# Senaino.net
KiCad netlist of a schematic drawn in EAGLE
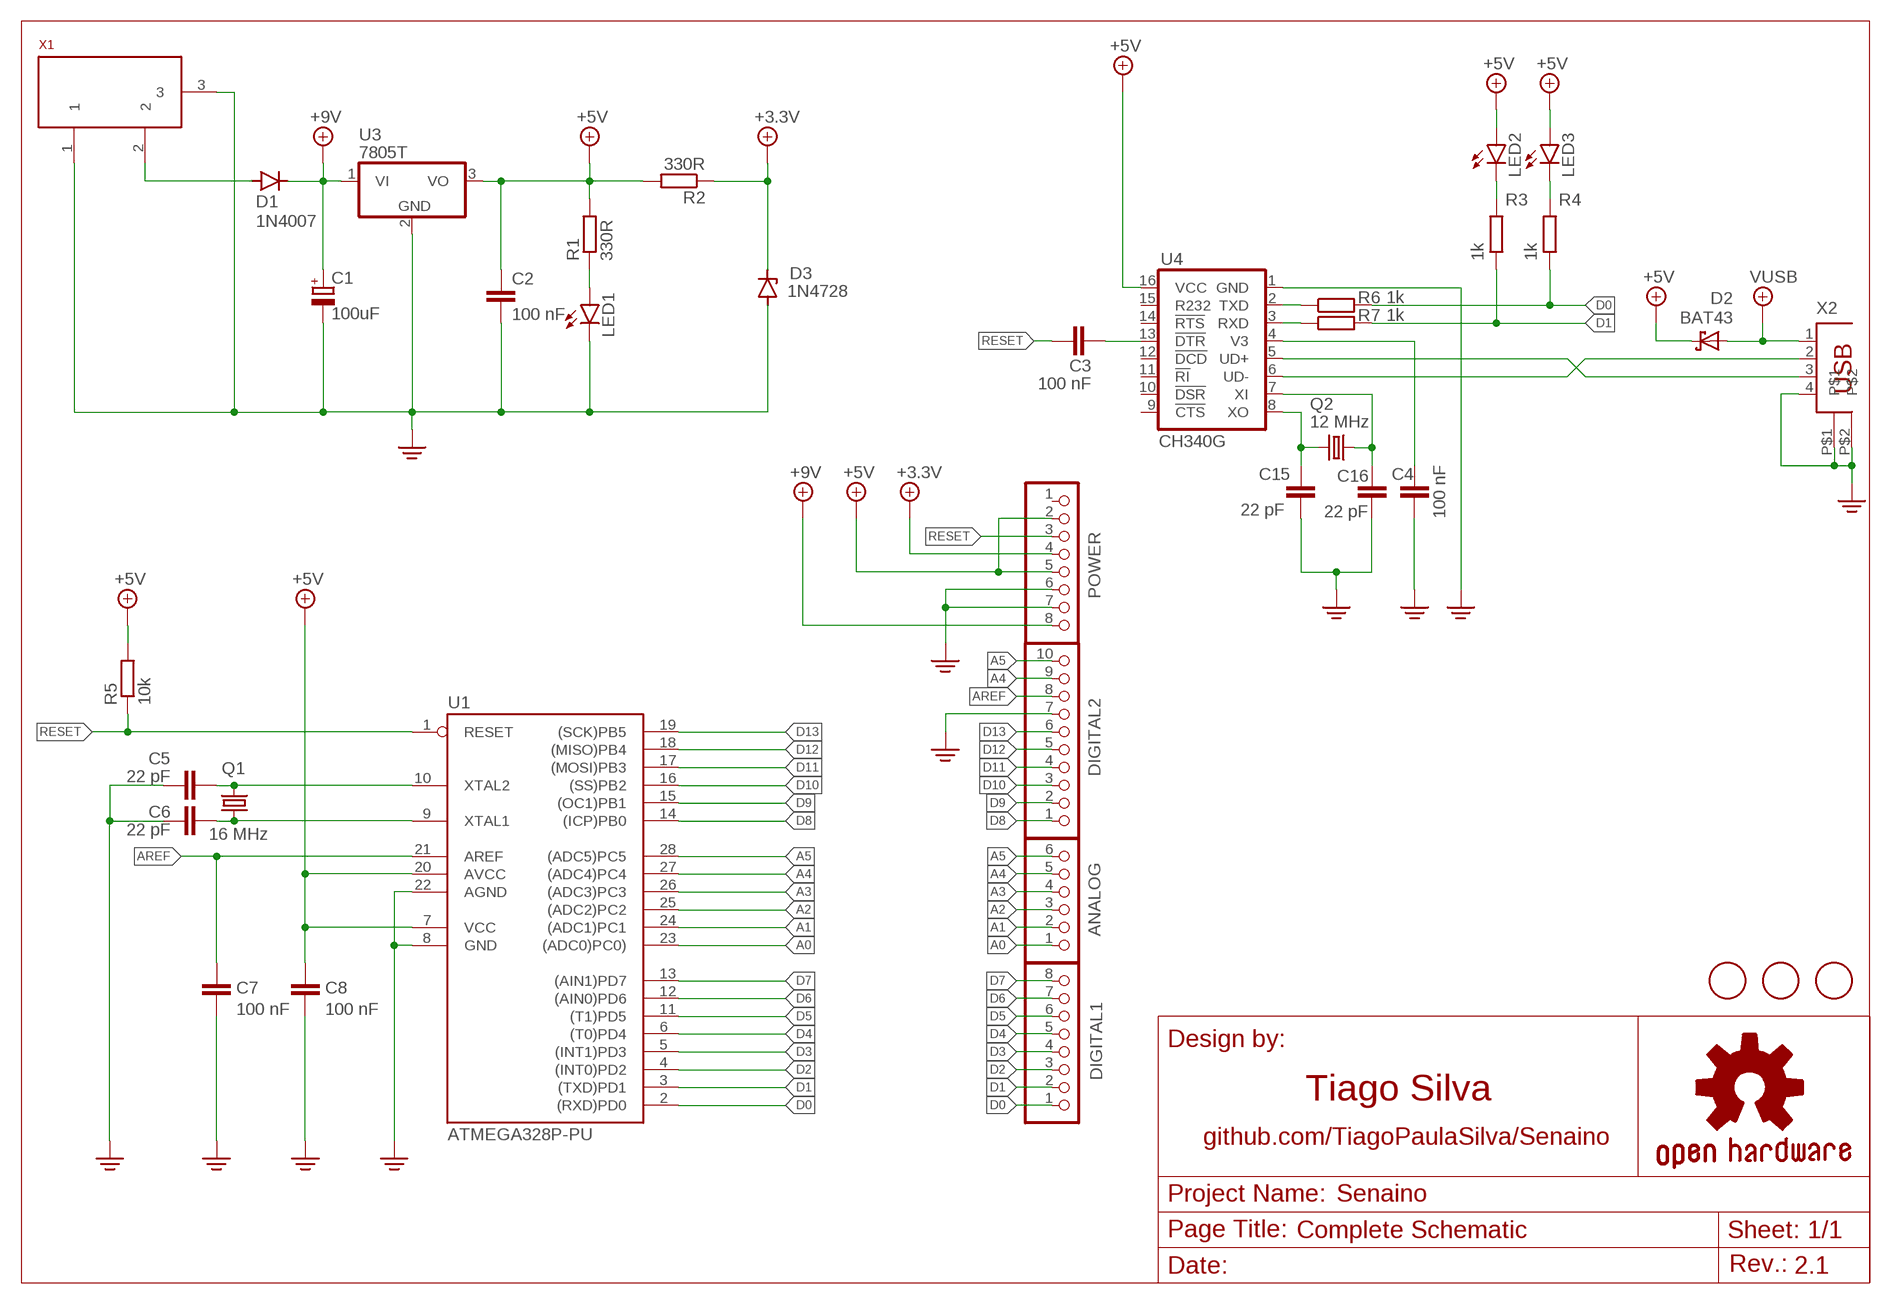
[diagram p0: schematic, sheet 1]

(export (version "E")
  (design (tool "Eeschema 10.0.6"))
  (components
    (comp (ref "ANALOG")
      (value "PINHD-1X6")
      (footprint "eagle-import:1X06")
      (libsource (lib "eagle-import") (part "PINHD-1X6"))
    )
    (comp (ref "C1")
      (value "100uF")
      (footprint "eagle-import:E2-5")
      (libsource (lib "eagle-import") (part "CPOL-EUE2-5"))
    )
    (comp (ref "C2")
      (value "100 nF")
      (footprint "eagle-import:C025-024X044")
      (libsource (lib "eagle-import") (part "C-EU025-024X044"))
    )
    (comp (ref "C3")
      (value "100 nF")
      (footprint "eagle-import:C025-024X044")
      (libsource (lib "eagle-import") (part "C-EU025-024X044"))
    )
    (comp (ref "C4")
      (value "100 nF")
      (footprint "eagle-import:C025-024X044")
      (libsource (lib "eagle-import") (part "C-EU025-024X044"))
    )
    (comp (ref "C5")
      (value "22 pF")
      (footprint "eagle-import:C025-024X044")
      (libsource (lib "eagle-import") (part "C-EU025-024X044"))
    )
    (comp (ref "C6")
      (value "22 pF")
      (footprint "eagle-import:C025-024X044")
      (libsource (lib "eagle-import") (part "C-EU025-024X044"))
    )
    (comp (ref "C7")
      (value "100 nF")
      (footprint "eagle-import:C025-024X044")
      (libsource (lib "eagle-import") (part "C-EU025-024X044"))
    )
    (comp (ref "C8")
      (value "100 nF")
      (footprint "eagle-import:C025-024X044")
      (libsource (lib "eagle-import") (part "C-EU025-024X044"))
    )
    (comp (ref "C15")
      (value "22 pF")
      (footprint "eagle-import:C025-024X044")
      (libsource (lib "eagle-import") (part "C-EU025-024X044"))
    )
    (comp (ref "C16")
      (value "22 pF")
      (footprint "eagle-import:C025-024X044")
      (libsource (lib "eagle-import") (part "C-EU025-024X044"))
    )
    (comp (ref "D1")
      (value "1N4007")
      (footprint "eagle-import:DO35-7")
      (libsource (lib "eagle-import") (part "1N4148DO35-7"))
    )
    (comp (ref "D2")
      (value "BAT43")
      (footprint "eagle-import:DIODE_DO35-7")
      (libsource (lib "eagle-import") (part "SCHOTTKY-DIODEDO35-7"))
    )
    (comp (ref "D3")
      (value "1N4728")
      (footprint "eagle-import:DO41Z10")
      (libsource (lib "eagle-import") (part "1N4728"))
    )
    (comp (ref "DIGITAL1")
      (value "PINHD-1X8")
      (footprint "eagle-import:1X08")
      (libsource (lib "eagle-import") (part "PINHD-1X8"))
    )
    (comp (ref "DIGITAL2")
      (value "PINHD-1X10_ARD")
      (footprint "eagle-import:1X10")
      (libsource (lib "eagle-import") (part "PINHD-1X10_ARD"))
    )
    (comp (ref "FD1")
      (value "FIDUCIALMOUNT")
      (footprint "eagle-import:FIDUCIA-MOUNT")
      (libsource (lib "eagle-import") (part "FIDUCIALMOUNT"))
    )
    (comp (ref "FD2")
      (value "FIDUCIALMOUNT")
      (footprint "eagle-import:FIDUCIA-MOUNT")
      (libsource (lib "eagle-import") (part "FIDUCIALMOUNT"))
    )
    (comp (ref "FD3")
      (value "FIDUCIALMOUNT")
      (footprint "eagle-import:FIDUCIA-MOUNT")
      (libsource (lib "eagle-import") (part "FIDUCIALMOUNT"))
    )
    (comp (ref "LED1")
      (value "LED3MM")
      (footprint "eagle-import:LED3MM")
      (libsource (lib "eagle-import") (part "LED3MM"))
    )
    (comp (ref "LED2")
      (value "LED3MM")
      (footprint "eagle-import:LED3MM")
      (libsource (lib "eagle-import") (part "LED3MM"))
    )
    (comp (ref "LED3")
      (value "LED3MM")
      (footprint "eagle-import:LED3MM")
      (libsource (lib "eagle-import") (part "LED3MM"))
    )
    (comp (ref "POWER")
      (value "PINHD-1X8")
      (footprint "eagle-import:1X08")
      (libsource (lib "eagle-import") (part "PINHD-1X8"))
    )
    (comp (ref "Q1")
      (value "16 MHz")
      (footprint "eagle-import:HC49_S")
      (libsource (lib "eagle-import") (part "CRYSTALHC49S"))
    )
    (comp (ref "Q2")
      (value "12 MHz")
      (footprint "eagle-import:HC49_S")
      (libsource (lib "eagle-import") (part "CRYSTALHC49S"))
    )
    (comp (ref "R1")
      (value "330R")
      (footprint "eagle-import:0204_7")
      (libsource (lib "eagle-import") (part "R-EU_0204/7"))
    )
    (comp (ref "R2")
      (value "330R")
      (footprint "eagle-import:0204_7")
      (libsource (lib "eagle-import") (part "R-EU_0204/7"))
    )
    (comp (ref "R3")
      (value "1k")
      (footprint "eagle-import:0204_7")
      (libsource (lib "eagle-import") (part "R-EU_0204/7"))
    )
    (comp (ref "R4")
      (value "1k")
      (footprint "eagle-import:0204_7")
      (libsource (lib "eagle-import") (part "R-EU_0204/7"))
    )
    (comp (ref "R5")
      (value "10k")
      (footprint "eagle-import:0204_7")
      (libsource (lib "eagle-import") (part "R-EU_0204/7"))
    )
    (comp (ref "R6")
      (value "1k")
      (footprint "eagle-import:0204_7")
      (libsource (lib "eagle-import") (part "R-EU_0204/7"))
    )
    (comp (ref "R7")
      (value "1k")
      (footprint "eagle-import:0204_7")
      (libsource (lib "eagle-import") (part "R-EU_0204/7"))
    )
    (comp (ref "U1")
      (value "ATMEGA328P-PU")
      (footprint "eagle-import:DIL28-3")
      (libsource (lib "eagle-import") (part "ATMEGA328P-PU"))
    )
    (comp (ref "U3")
      (value "7805T")
      (footprint "eagle-import:TO220H")
      (libsource (lib "eagle-import") (part "78T05"))
    )
    (comp (ref "U4")
      (value "CH340G")
      (footprint "eagle-import:SO016")
      (libsource (lib "eagle-import") (part "CH340GSMD"))
    )
    (comp (ref "X1")
      (value "POWERSUPPLY_DC21MMX")
      (footprint "eagle-import:POWERSUPPLY_DC-21MM")
      (libsource (lib "eagle-import") (part "POWERSUPPLY_DC21MMX"))
    )
    (comp (ref "X2")
      (value "PN61729")
      (footprint "eagle-import:PN61729")
      (libsource (lib "eagle-import") (part "PN61729"))
    )
  )
  (nets
    (net (code "1") (name "+3.3V") (class "Default")
      (node (ref "D3") (pin "C") (pinfunction "C_C") (pintype "passive"))
      (node (ref "POWER") (pin "4") (pinfunction "4_4") (pintype "passive"))
      (node (ref "R2") (pin "1") (pinfunction "1_1") (pintype "passive"))
    )
    (net (code "2") (name "+5V") (class "Default")
      (node (ref "C2") (pin "1") (pinfunction "1_1") (pintype "passive"))
      (node (ref "C8") (pin "1") (pinfunction "1_1") (pintype "passive"))
      (node (ref "D2") (pin "C") (pinfunction "A_C") (pintype "passive"))
      (node (ref "LED2") (pin "A") (pinfunction "A_A") (pintype "passive"))
      (node (ref "LED3") (pin "A") (pinfunction "A_A") (pintype "passive"))
      (node (ref "POWER") (pin "2") (pinfunction "2_2") (pintype "passive"))
      (node (ref "POWER") (pin "5") (pinfunction "5_5") (pintype "passive"))
      (node (ref "R1") (pin "2") (pinfunction "2_2") (pintype "passive"))
      (node (ref "R2") (pin "2") (pinfunction "2_2") (pintype "passive"))
      (node (ref "R5") (pin "2") (pinfunction "2_2") (pintype "passive"))
      (node (ref "U1") (pin "20") (pinfunction "AVCC_20") (pintype "power_in"))
      (node (ref "U1") (pin "7") (pinfunction "VCC_7") (pintype "power_in"))
      (node (ref "U3") (pin "3") (pinfunction "VO_3") (pintype "passive"))
      (node (ref "U4") (pin "16") (pinfunction "VCC_16") (pintype "bidirectional"))
    )
    (net (code "3") (name "+9V") (class "Default")
      (node (ref "C1") (pin "+") (pinfunction "+_+") (pintype "passive"))
      (node (ref "D1") (pin "C") (pinfunction "C_C") (pintype "passive"))
      (node (ref "POWER") (pin "8") (pinfunction "8_8") (pintype "passive"))
      (node (ref "U3") (pin "1") (pinfunction "VI_1") (pintype "input"))
    )
    (net (code "4") (name "A0") (class "Default")
      (node (ref "ANALOG") (pin "1") (pinfunction "1_1") (pintype "passive"))
      (node (ref "U1") (pin "23") (pinfunction "(ADC0)PC0)_23") (pintype "bidirectional"))
    )
    (net (code "5") (name "A1") (class "Default")
      (node (ref "ANALOG") (pin "2") (pinfunction "2_2") (pintype "passive"))
      (node (ref "U1") (pin "24") (pinfunction "(ADC1)PC1_24") (pintype "bidirectional"))
    )
    (net (code "6") (name "A2") (class "Default")
      (node (ref "ANALOG") (pin "3") (pinfunction "3_3") (pintype "passive"))
      (node (ref "U1") (pin "25") (pinfunction "(ADC2)PC2_25") (pintype "bidirectional"))
    )
    (net (code "7") (name "A3") (class "Default")
      (node (ref "ANALOG") (pin "4") (pinfunction "4_4") (pintype "passive"))
      (node (ref "U1") (pin "26") (pinfunction "(ADC3)PC3_26") (pintype "bidirectional"))
    )
    (net (code "8") (name "A4") (class "Default")
      (node (ref "ANALOG") (pin "5") (pinfunction "5_5") (pintype "passive"))
      (node (ref "DIGITAL2") (pin "9") (pinfunction "9_9") (pintype "passive"))
      (node (ref "U1") (pin "27") (pinfunction "(ADC4)PC4_27") (pintype "bidirectional"))
    )
    (net (code "9") (name "A5") (class "Default")
      (node (ref "ANALOG") (pin "6") (pinfunction "6_6") (pintype "passive"))
      (node (ref "DIGITAL2") (pin "10") (pinfunction "10_10") (pintype "passive"))
      (node (ref "U1") (pin "28") (pinfunction "(ADC5)PC5_28") (pintype "bidirectional"))
    )
    (net (code "10") (name "AREF") (class "Default")
      (node (ref "C7") (pin "1") (pinfunction "1_1") (pintype "passive"))
      (node (ref "DIGITAL2") (pin "8") (pinfunction "8_8") (pintype "passive"))
      (node (ref "U1") (pin "21") (pinfunction "AREF_21") (pintype "passive"))
    )
    (net (code "11") (name "D0") (class "Default")
      (node (ref "DIGITAL1") (pin "1") (pinfunction "1_1") (pintype "passive"))
      (node (ref "R4") (pin "1") (pinfunction "1_1") (pintype "passive"))
      (node (ref "R6") (pin "2") (pinfunction "2_2") (pintype "passive"))
      (node (ref "U1") (pin "2") (pinfunction "(RXD)PD0_2") (pintype "bidirectional"))
    )
    (net (code "12") (name "D1") (class "Default")
      (node (ref "DIGITAL1") (pin "2") (pinfunction "2_2") (pintype "passive"))
      (node (ref "R3") (pin "1") (pinfunction "1_1") (pintype "passive"))
      (node (ref "R7") (pin "2") (pinfunction "2_2") (pintype "passive"))
      (node (ref "U1") (pin "3") (pinfunction "(TXD)PD1_3") (pintype "bidirectional"))
    )
    (net (code "13") (name "D2") (class "Default")
      (node (ref "DIGITAL1") (pin "3") (pinfunction "3_3") (pintype "passive"))
      (node (ref "U1") (pin "4") (pinfunction "(INT0)PD2_4") (pintype "bidirectional"))
    )
    (net (code "14") (name "D3") (class "Default")
      (node (ref "DIGITAL1") (pin "4") (pinfunction "4_4") (pintype "passive"))
      (node (ref "U1") (pin "5") (pinfunction "(INT1)PD3_5") (pintype "bidirectional"))
    )
    (net (code "15") (name "D4") (class "Default")
      (node (ref "DIGITAL1") (pin "5") (pinfunction "5_5") (pintype "passive"))
      (node (ref "U1") (pin "6") (pinfunction "(T0)PD4_6") (pintype "bidirectional"))
    )
    (net (code "16") (name "D5") (class "Default")
      (node (ref "DIGITAL1") (pin "6") (pinfunction "6_6") (pintype "passive"))
      (node (ref "U1") (pin "11") (pinfunction "(T1)PD5_11") (pintype "bidirectional"))
    )
    (net (code "17") (name "D6") (class "Default")
      (node (ref "DIGITAL1") (pin "7") (pinfunction "7_7") (pintype "passive"))
      (node (ref "U1") (pin "12") (pinfunction "(AIN0)PD6_12") (pintype "bidirectional"))
    )
    (net (code "18") (name "D7") (class "Default")
      (node (ref "DIGITAL1") (pin "8") (pinfunction "8_8") (pintype "passive"))
      (node (ref "U1") (pin "13") (pinfunction "(AIN1)PD7_13") (pintype "bidirectional"))
    )
    (net (code "19") (name "D8") (class "Default")
      (node (ref "DIGITAL2") (pin "1") (pinfunction "1_1") (pintype "passive"))
      (node (ref "U1") (pin "14") (pinfunction "(ICP)PB0_14") (pintype "bidirectional"))
    )
    (net (code "20") (name "D9") (class "Default")
      (node (ref "DIGITAL2") (pin "2") (pinfunction "2_2") (pintype "passive"))
      (node (ref "U1") (pin "15") (pinfunction "(OC1)PB1_15") (pintype "bidirectional"))
    )
    (net (code "21") (name "D10") (class "Default")
      (node (ref "DIGITAL2") (pin "3") (pinfunction "3_3") (pintype "passive"))
      (node (ref "U1") (pin "16") (pinfunction "(SS)PB2_16") (pintype "bidirectional"))
    )
    (net (code "22") (name "D11") (class "Default")
      (node (ref "DIGITAL2") (pin "4") (pinfunction "4_4") (pintype "passive"))
      (node (ref "U1") (pin "17") (pinfunction "(MOSI)PB3_17") (pintype "bidirectional"))
    )
    (net (code "23") (name "D12") (class "Default")
      (node (ref "DIGITAL2") (pin "5") (pinfunction "5_5") (pintype "passive"))
      (node (ref "U1") (pin "18") (pinfunction "(MISO)PB4_18") (pintype "bidirectional"))
    )
    (net (code "24") (name "D13") (class "Default")
      (node (ref "DIGITAL2") (pin "6") (pinfunction "6_6") (pintype "passive"))
      (node (ref "U1") (pin "19") (pinfunction "(SCK)PB5_19") (pintype "bidirectional"))
    )
    (net (code "25") (name "GND") (class "Default")
      (node (ref "C1") (pin "-") (pinfunction "-_-") (pintype "passive"))
      (node (ref "C15") (pin "1") (pinfunction "1_1") (pintype "passive"))
      (node (ref "C16") (pin "1") (pinfunction "1_1") (pintype "passive"))
      (node (ref "C2") (pin "2") (pinfunction "2_2") (pintype "passive"))
      (node (ref "C4") (pin "1") (pinfunction "1_1") (pintype "passive"))
      (node (ref "C5") (pin "1") (pinfunction "1_1") (pintype "passive"))
      (node (ref "C6") (pin "1") (pinfunction "1_1") (pintype "passive"))
      (node (ref "C7") (pin "2") (pinfunction "2_2") (pintype "passive"))
      (node (ref "C8") (pin "2") (pinfunction "2_2") (pintype "passive"))
      (node (ref "D3") (pin "A") (pinfunction "A_A") (pintype "passive"))
      (node (ref "DIGITAL2") (pin "7") (pinfunction "7_7") (pintype "passive"))
      (node (ref "LED1") (pin "K") (pinfunction "C_K") (pintype "passive"))
      (node (ref "POWER") (pin "6") (pinfunction "6_6") (pintype "passive"))
      (node (ref "POWER") (pin "7") (pinfunction "7_7") (pintype "passive"))
      (node (ref "U1") (pin "22") (pinfunction "AGND_22") (pintype "power_in"))
      (node (ref "U1") (pin "8") (pinfunction "GND_8") (pintype "power_in"))
      (node (ref "U3") (pin "2") (pinfunction "GND_2") (pintype "passive"))
      (node (ref "U4") (pin "1") (pinfunction "GND_1") (pintype "bidirectional"))
      (node (ref "X1") (pin "1") (pinfunction "1_1") (pintype "power_in"))
      (node (ref "X1") (pin "3") (pinfunction "3_3") (pintype "power_in"))
      (node (ref "X2") (pin "4") (pinfunction "4_4") (pintype "bidirectional"))
      (node (ref "X2") (pin "P$1") (pinfunction "P$1_P$1") (pintype "bidirectional"))
      (node (ref "X2") (pin "P$2") (pinfunction "P$2_P$2") (pintype "bidirectional"))
    )
    (net (code "26") (name "Net-(D1-PadA)") (class "Default")
      (node (ref "D1") (pin "A") (pinfunction "A_A") (pintype "passive"))
      (node (ref "X1") (pin "2") (pinfunction "2_2") (pintype "power_in"))
    )
    (net (code "27") (name "Net-(LED1-PadA)") (class "Default")
      (node (ref "LED1") (pin "A") (pinfunction "A_A") (pintype "passive"))
      (node (ref "R1") (pin "1") (pinfunction "1_1") (pintype "passive"))
    )
    (net (code "28") (name "Net-(LED2-C)") (class "Default")
      (node (ref "LED2") (pin "K") (pinfunction "C_K") (pintype "passive"))
      (node (ref "R3") (pin "2") (pinfunction "2_2") (pintype "passive"))
    )
    (net (code "29") (name "Net-(LED3-C)") (class "Default")
      (node (ref "LED3") (pin "K") (pinfunction "C_K") (pintype "passive"))
      (node (ref "R4") (pin "2") (pinfunction "2_2") (pintype "passive"))
    )
    (net (code "30") (name "Net-(U1-XTAL1)") (class "Default")
      (node (ref "C6") (pin "2") (pinfunction "2_2") (pintype "passive"))
      (node (ref "Q1") (pin "1") (pinfunction "1_1") (pintype "passive"))
      (node (ref "U1") (pin "9") (pinfunction "XTAL1_9") (pintype "bidirectional"))
    )
    (net (code "31") (name "Net-(U1-XTAL2)") (class "Default")
      (node (ref "C5") (pin "2") (pinfunction "2_2") (pintype "passive"))
      (node (ref "Q1") (pin "2") (pinfunction "2_2") (pintype "passive"))
      (node (ref "U1") (pin "10") (pinfunction "XTAL2_10") (pintype "bidirectional"))
    )
    (net (code "32") (name "Net-(U4-RXD)") (class "Default")
      (node (ref "R7") (pin "1") (pinfunction "1_1") (pintype "passive"))
      (node (ref "U4") (pin "3") (pinfunction "RXD_3") (pintype "bidirectional"))
    )
    (net (code "33") (name "Net-(U4-TXD)") (class "Default")
      (node (ref "R6") (pin "1") (pinfunction "1_1") (pintype "passive"))
      (node (ref "U4") (pin "2") (pinfunction "TXD_2") (pintype "bidirectional"))
    )
    (net (code "34") (name "Net-(U4-UD+)") (class "Default")
      (node (ref "U4") (pin "5") (pinfunction "UD+_5") (pintype "bidirectional"))
      (node (ref "X2") (pin "3") (pinfunction "3_3") (pintype "bidirectional"))
    )
    (net (code "35") (name "Net-(U4-UD-)") (class "Default")
      (node (ref "U4") (pin "6") (pinfunction "UD-_6") (pintype "bidirectional"))
      (node (ref "X2") (pin "2") (pinfunction "2_2") (pintype "bidirectional"))
    )
    (net (code "36") (name "Net-(U4-V3)") (class "Default")
      (node (ref "C4") (pin "2") (pinfunction "2_2") (pintype "passive"))
      (node (ref "U4") (pin "4") (pinfunction "V3_4") (pintype "bidirectional"))
    )
    (net (code "37") (name "Net-(U4-XI)") (class "Default")
      (node (ref "C16") (pin "2") (pinfunction "2_2") (pintype "passive"))
      (node (ref "Q2") (pin "1") (pinfunction "1_1") (pintype "passive"))
      (node (ref "U4") (pin "7") (pinfunction "XI_7") (pintype "bidirectional"))
    )
    (net (code "38") (name "Net-(U4-XO)") (class "Default")
      (node (ref "C15") (pin "2") (pinfunction "2_2") (pintype "passive"))
      (node (ref "Q2") (pin "2") (pinfunction "2_2") (pintype "passive"))
      (node (ref "U4") (pin "8") (pinfunction "XO_8") (pintype "bidirectional"))
    )
    (net (code "39") (name "Net-(U4-~{DTR})") (class "Default")
      (node (ref "C3") (pin "2") (pinfunction "2_2") (pintype "passive"))
      (node (ref "U4") (pin "13") (pinfunction "~{DTR}_13") (pintype "bidirectional"))
    )
    (net (code "40") (name "RESET") (class "Default")
      (node (ref "C3") (pin "1") (pinfunction "1_1") (pintype "passive"))
      (node (ref "POWER") (pin "3") (pinfunction "3_3") (pintype "passive"))
      (node (ref "R5") (pin "1") (pinfunction "1_1") (pintype "passive"))
      (node (ref "U1") (pin "1") (pinfunction "RESET_1") (pintype "input"))
    )
    (net (code "41") (name "VUSB") (class "Default")
      (node (ref "D2") (pin "A") (pinfunction "C_A") (pintype "passive"))
      (node (ref "X2") (pin "1") (pinfunction "1_1") (pintype "bidirectional"))
    )
    (net (code "42") (name "unconnected-(POWER-Pad1)") (class "Default")
      (node (ref "POWER") (pin "1") (pinfunction "1_1") (pintype "passive"))
    )
    (net (code "43") (name "unconnected-(U4-R232-Pad15)") (class "Default")
      (node (ref "U4") (pin "15") (pinfunction "R232_15") (pintype "bidirectional"))
    )
    (net (code "44") (name "unconnected-(U4-~{CTS}-Pad9)") (class "Default")
      (node (ref "U4") (pin "9") (pinfunction "~{CTS}_9") (pintype "bidirectional"))
    )
    (net (code "45") (name "unconnected-(U4-~{DCD}-Pad12)") (class "Default")
      (node (ref "U4") (pin "12") (pinfunction "~{DCD}_12") (pintype "bidirectional"))
    )
    (net (code "46") (name "unconnected-(U4-~{DSR}-Pad10)") (class "Default")
      (node (ref "U4") (pin "10") (pinfunction "~{DSR}_10") (pintype "bidirectional"))
    )
    (net (code "47") (name "unconnected-(U4-~{RI}-Pad11)") (class "Default")
      (node (ref "U4") (pin "11") (pinfunction "~{RI}_11") (pintype "bidirectional"))
    )
    (net (code "48") (name "unconnected-(U4-~{RTS}-Pad14)") (class "Default")
      (node (ref "U4") (pin "14") (pinfunction "~{RTS}_14") (pintype "bidirectional"))
    )
  )
)
